# DM2097_BOOT_AUX_uSD.net
KiCad netlist of a schematic drawn in Altium Designer
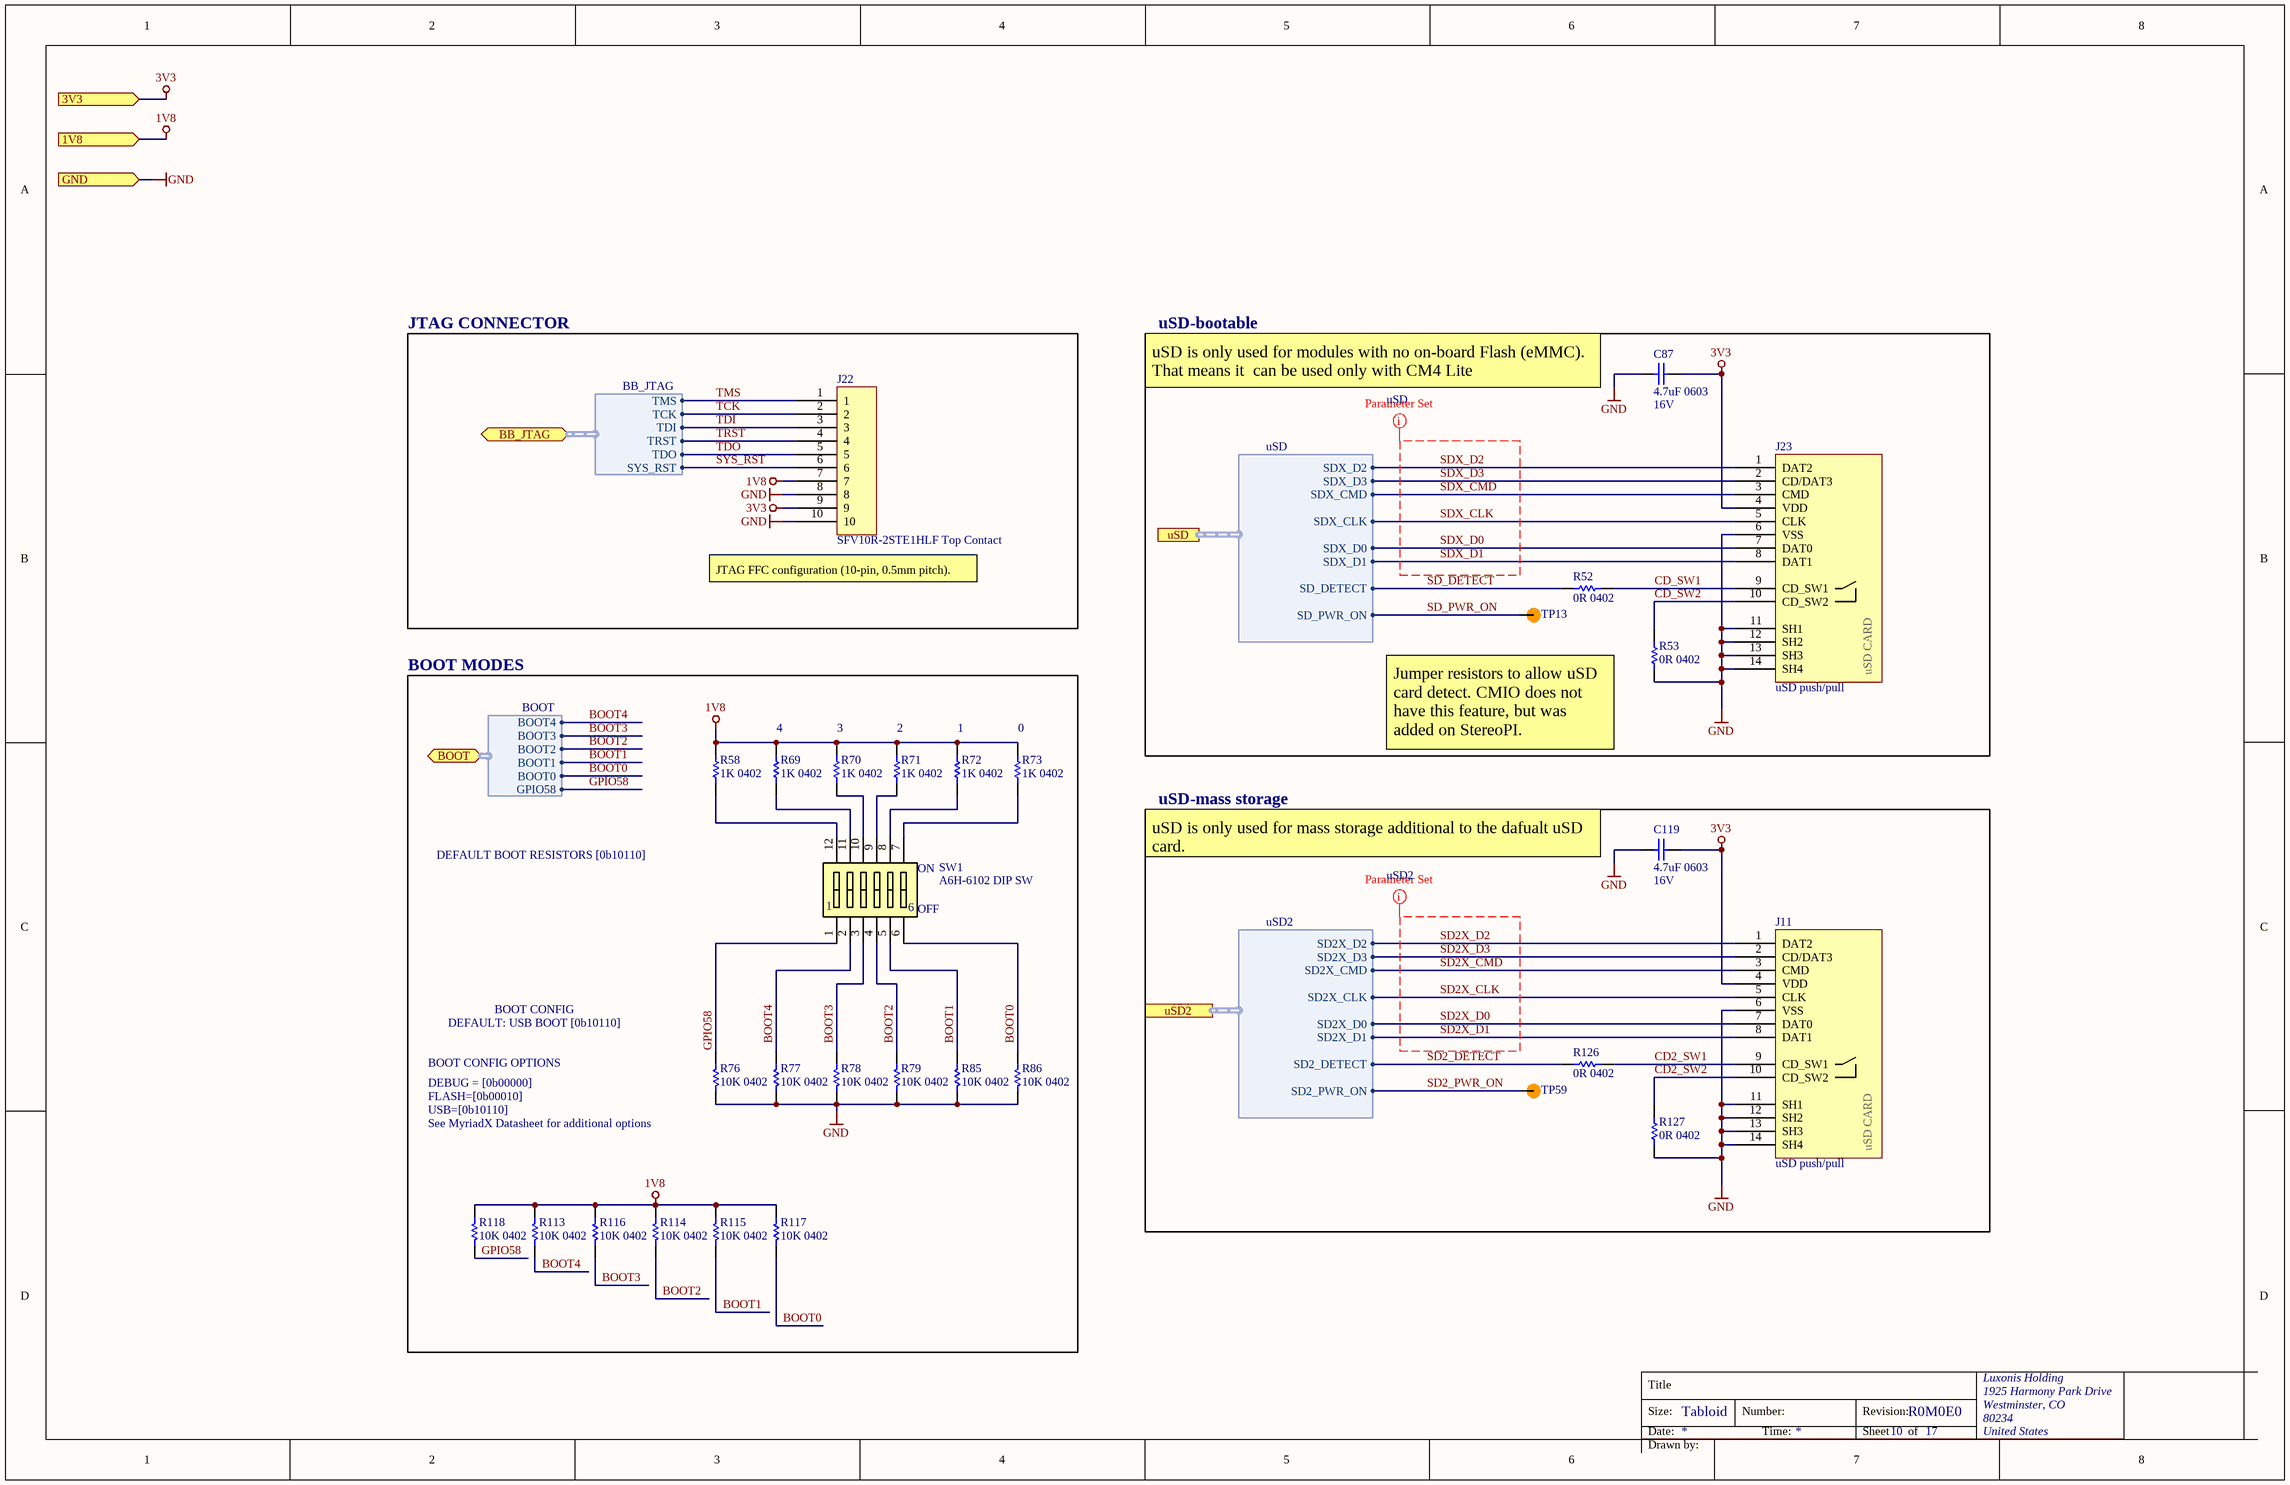
[diagram p0: DM2097_BOOT_AUX_uSD.SchDoc]

(export (version "E")
  (design (tool "Eeschema 10.0.6"))
  (components
    (comp (ref "C87")
      (value "4.7uF 0603")
      (footprint "CAP_Altium_Vault_Generic:CAPC0603(1608)100_N")
      (description "CAP CER 4.7UF 16V X5R 0603 10%")
      (fields (field (name "TOLERANCE") "10%") (field (name "VOLTAGE RATING") "16V"))
      (libsource (lib "LuxonisMaster") (part "GRM188R61C475KAAJD"))
    )
    (comp (ref "C119")
      (value "4.7uF 0603")
      (footprint "CAP_Altium_Vault_Generic:CAPC0603(1608)100_N")
      (description "CAP CER 4.7UF 16V X5R 0603 10%")
      (fields (field (name "TOLERANCE") "10%") (field (name "VOLTAGE RATING") "16V"))
      (libsource (lib "LuxonisMaster") (part "GRM188R61C475KAAJD"))
    )
    (comp (ref "J11")
      (value "uSD push/pull")
      (footprint "LuxonisMaster:104031-0811")
      (description "CONN MICRO SD CARD PUSH-PULL R/A")
      (libsource (lib "LuxonisMaster") (part "104031-0811"))
    )
    (comp (ref "J22")
      (value "SFV10R-2STE1HLF Top Contact")
      (footprint "LuxonisMaster:SFV10R-2STE1HLF")
      (description "CONN FFC TOP 10POS 0.50MM R/A")
      (libsource (lib "LuxonisMaster") (part "SFV10R-2STE1HLF"))
    )
    (comp (ref "J23")
      (value "uSD push/pull")
      (footprint "LuxonisMaster:104031-0811")
      (description "CONN MICRO SD CARD PUSH-PULL R/A")
      (libsource (lib "LuxonisMaster") (part "104031-0811"))
    )
    (comp (ref "R52")
      (value "0R 0402")
      (footprint "RES_Altium_Vault_Generic:RESC0402(1005)_N")
      (description "RES SMD 0 OHM JUMPER 1/16W 0402")
      (fields (field (name "TOLERANCE") "5%"))
      (libsource (lib "LuxonisMaster") (part "CRCW04020000Z0ED"))
    )
    (comp (ref "R53")
      (value "0R 0402")
      (footprint "RES_Altium_Vault_Generic:RESC0402(1005)_N")
      (description "RES SMD 0 OHM JUMPER 1/16W 0402")
      (fields (field (name "TOLERANCE") "5%"))
      (libsource (lib "LuxonisMaster") (part "CRCW04020000Z0ED"))
    )
    (comp (ref "R58")
      (value "1K 0402")
      (footprint "RES_Altium_Vault_Generic:RESC0402(1005)_N")
      (fields (field (name "TOLERANCE") "1%"))
      (libsource (lib "LuxonisMaster") (part "RC0402FR-071KL"))
    )
    (comp (ref "R69")
      (value "1K 0402")
      (footprint "RES_Altium_Vault_Generic:RESC0402(1005)_N")
      (fields (field (name "TOLERANCE") "1%"))
      (libsource (lib "LuxonisMaster") (part "RC0402FR-071KL"))
    )
    (comp (ref "R70")
      (value "1K 0402")
      (footprint "RES_Altium_Vault_Generic:RESC0402(1005)_N")
      (fields (field (name "TOLERANCE") "1%"))
      (libsource (lib "LuxonisMaster") (part "RC0402FR-071KL"))
    )
    (comp (ref "R71")
      (value "1K 0402")
      (footprint "RES_Altium_Vault_Generic:RESC0402(1005)_N")
      (fields (field (name "TOLERANCE") "1%"))
      (libsource (lib "LuxonisMaster") (part "RC0402FR-071KL"))
    )
    (comp (ref "R72")
      (value "1K 0402")
      (footprint "RES_Altium_Vault_Generic:RESC0402(1005)_N")
      (fields (field (name "TOLERANCE") "1%"))
      (libsource (lib "LuxonisMaster") (part "RC0402FR-071KL"))
    )
    (comp (ref "R73")
      (value "1K 0402")
      (footprint "RES_Altium_Vault_Generic:RESC0402(1005)_N")
      (fields (field (name "TOLERANCE") "1%"))
      (libsource (lib "LuxonisMaster") (part "RC0402FR-071KL"))
    )
    (comp (ref "R76")
      (value "10K 0402")
      (footprint "RES_Altium_Vault_Generic:RESC0402(1005)_N")
      (fields (field (name "TOLERANCE") "1%"))
      (libsource (lib "LuxonisMaster") (part "RC0402FR-1310KL"))
    )
    (comp (ref "R77")
      (value "10K 0402")
      (footprint "RES_Altium_Vault_Generic:RESC0402(1005)_N")
      (fields (field (name "TOLERANCE") "1%"))
      (libsource (lib "LuxonisMaster") (part "RC0402FR-1310KL"))
    )
    (comp (ref "R78")
      (value "10K 0402")
      (footprint "RES_Altium_Vault_Generic:RESC0402(1005)_N")
      (fields (field (name "TOLERANCE") "1%"))
      (libsource (lib "LuxonisMaster") (part "RC0402FR-1310KL"))
    )
    (comp (ref "R79")
      (value "10K 0402")
      (footprint "RES_Altium_Vault_Generic:RESC0402(1005)_N")
      (fields (field (name "TOLERANCE") "1%"))
      (libsource (lib "LuxonisMaster") (part "RC0402FR-1310KL"))
    )
    (comp (ref "R85")
      (value "10K 0402")
      (footprint "RES_Altium_Vault_Generic:RESC0402(1005)_N")
      (fields (field (name "TOLERANCE") "1%"))
      (libsource (lib "LuxonisMaster") (part "RC0402FR-1310KL"))
    )
    (comp (ref "R86")
      (value "10K 0402")
      (footprint "RES_Altium_Vault_Generic:RESC0402(1005)_N")
      (fields (field (name "TOLERANCE") "1%"))
      (libsource (lib "LuxonisMaster") (part "RC0402FR-1310KL"))
    )
    (comp (ref "R113")
      (value "10K 0402")
      (footprint "RES_Altium_Vault_Generic:RESC0402(1005)_N")
      (fields (field (name "TOLERANCE") "1%"))
      (libsource (lib "LuxonisMaster") (part "RC0402FR-1310KL"))
    )
    (comp (ref "R114")
      (value "10K 0402")
      (footprint "RES_Altium_Vault_Generic:RESC0402(1005)_N")
      (fields (field (name "TOLERANCE") "1%"))
      (libsource (lib "LuxonisMaster") (part "RC0402FR-1310KL"))
    )
    (comp (ref "R115")
      (value "10K 0402")
      (footprint "RES_Altium_Vault_Generic:RESC0402(1005)_N")
      (fields (field (name "TOLERANCE") "1%"))
      (libsource (lib "LuxonisMaster") (part "RC0402FR-1310KL"))
    )
    (comp (ref "R116")
      (value "10K 0402")
      (footprint "RES_Altium_Vault_Generic:RESC0402(1005)_N")
      (fields (field (name "TOLERANCE") "1%"))
      (libsource (lib "LuxonisMaster") (part "RC0402FR-1310KL"))
    )
    (comp (ref "R117")
      (value "10K 0402")
      (footprint "RES_Altium_Vault_Generic:RESC0402(1005)_N")
      (fields (field (name "TOLERANCE") "1%"))
      (libsource (lib "LuxonisMaster") (part "RC0402FR-1310KL"))
    )
    (comp (ref "R118")
      (value "10K 0402")
      (footprint "RES_Altium_Vault_Generic:RESC0402(1005)_N")
      (fields (field (name "TOLERANCE") "1%"))
      (libsource (lib "LuxonisMaster") (part "RC0402FR-1310KL"))
    )
    (comp (ref "R126")
      (value "0R 0402")
      (footprint "RES_Altium_Vault_Generic:RESC0402(1005)_N")
      (description "RES SMD 0 OHM JUMPER 1/16W 0402")
      (fields (field (name "TOLERANCE") "5%"))
      (libsource (lib "LuxonisMaster") (part "CRCW04020000Z0ED"))
    )
    (comp (ref "R127")
      (value "0R 0402")
      (footprint "RES_Altium_Vault_Generic:RESC0402(1005)_N")
      (description "RES SMD 0 OHM JUMPER 1/16W 0402")
      (fields (field (name "TOLERANCE") "5%"))
      (libsource (lib "LuxonisMaster") (part "CRCW04020000Z0ED"))
    )
    (comp (ref "SW1")
      (value "A6H-6102 DIP SW")
      (footprint "LuxonisMaster:A6H-610x")
      (description "SWITCH SLIDE DIP SPST 25MA 24V (SEALED)")
      (libsource (lib "LuxonisMaster") (part "A6H-6102"))
    )
    (comp (ref "TP13")
      (value "TP100_200_NS")
      (footprint "LuxonisMaster:TP100_200_NS")
      (libsource (lib "LuxonisMaster") (part "TEST_POINT"))
    )
    (comp (ref "TP59")
      (value "TP100_200_NS")
      (footprint "LuxonisMaster:TP100_200_NS")
      (libsource (lib "LuxonisMaster") (part "TEST_POINT"))
    )
  )
  (nets
    (net (code "5") (name "/BOOT0") (class "Default")
      (node (ref "R117") (pin "2") (pinfunction "2_2") (pintype "passive"))
      (node (ref "R86") (pin "1") (pinfunction "1_1") (pintype "passive"))
      (node (ref "SW1") (pin "6") (pinfunction "6_6") (pintype "passive"))
    )
    (net (code "6") (name "/BOOT1") (class "Default")
      (node (ref "R115") (pin "2") (pinfunction "2_2") (pintype "passive"))
      (node (ref "R85") (pin "1") (pinfunction "1_1") (pintype "passive"))
      (node (ref "SW1") (pin "5") (pinfunction "5_5") (pintype "passive"))
    )
    (net (code "7") (name "/BOOT2") (class "Default")
      (node (ref "R114") (pin "2") (pinfunction "2_2") (pintype "passive"))
      (node (ref "R79") (pin "1") (pinfunction "1_1") (pintype "passive"))
      (node (ref "SW1") (pin "4") (pinfunction "4_4") (pintype "passive"))
    )
    (net (code "8") (name "/BOOT3") (class "Default")
      (node (ref "R116") (pin "2") (pinfunction "2_2") (pintype "passive"))
      (node (ref "R78") (pin "1") (pinfunction "1_1") (pintype "passive"))
      (node (ref "SW1") (pin "3") (pinfunction "3_3") (pintype "passive"))
    )
    (net (code "9") (name "/BOOT4") (class "Default")
      (node (ref "R113") (pin "2") (pinfunction "2_2") (pintype "passive"))
      (node (ref "R77") (pin "1") (pinfunction "1_1") (pintype "passive"))
      (node (ref "SW1") (pin "2") (pinfunction "2_2") (pintype "passive"))
    )
    (net (code "10") (name "/CD2_SW1") (class "Default")
      (node (ref "J11") (pin "9") (pinfunction "CD_SW1_9") (pintype "passive"))
      (node (ref "R126") (pin "1") (pinfunction "1_1") (pintype "passive"))
    )
    (net (code "11") (name "/CD2_SW2") (class "Default")
      (node (ref "J11") (pin "10") (pinfunction "CD_SW2_10") (pintype "passive"))
      (node (ref "R127") (pin "2") (pinfunction "2_2") (pintype "passive"))
    )
    (net (code "12") (name "/CD_SW1") (class "Default")
      (node (ref "J23") (pin "9") (pinfunction "CD_SW1_9") (pintype "passive"))
      (node (ref "R52") (pin "1") (pinfunction "1_1") (pintype "passive"))
    )
    (net (code "13") (name "/CD_SW2") (class "Default")
      (node (ref "J23") (pin "10") (pinfunction "CD_SW2_10") (pintype "passive"))
      (node (ref "R53") (pin "2") (pinfunction "2_2") (pintype "passive"))
    )
    (net (code "14") (name "/GPIO58") (class "Default")
      (node (ref "R118") (pin "2") (pinfunction "2_2") (pintype "passive"))
      (node (ref "R76") (pin "1") (pinfunction "1_1") (pintype "passive"))
      (node (ref "SW1") (pin "1") (pinfunction "1_1") (pintype "passive"))
    )
    (net (code "15") (name "/SD2X_CLK") (class "Default")
      (node (ref "J11") (pin "5") (pinfunction "CLK_5") (pintype "passive"))
    )
    (net (code "16") (name "/SD2X_CMD") (class "Default")
      (node (ref "J11") (pin "3") (pinfunction "CMD_3") (pintype "passive"))
    )
    (net (code "17") (name "/SD2X_D0") (class "Default")
      (node (ref "J11") (pin "7") (pinfunction "DAT0_7") (pintype "passive"))
    )
    (net (code "18") (name "/SD2X_D1") (class "Default")
      (node (ref "J11") (pin "8") (pinfunction "DAT1_8") (pintype "passive"))
    )
    (net (code "19") (name "/SD2X_D2") (class "Default")
      (node (ref "J11") (pin "1") (pinfunction "DAT2_1") (pintype "passive"))
    )
    (net (code "20") (name "/SD2X_D3") (class "Default")
      (node (ref "J11") (pin "2") (pinfunction "CD/DAT3_2") (pintype "passive"))
    )
    (net (code "21") (name "/SD2_DETECT") (class "Default")
      (node (ref "R126") (pin "2") (pinfunction "2_2") (pintype "passive"))
    )
    (net (code "22") (name "/SD2_PWR_ON") (class "Default") (node (ref "TP59") (pin "1") (pintype "passive")))
    (net (code "23") (name "/SDX_CLK") (class "Default")
      (node (ref "J23") (pin "5") (pinfunction "CLK_5") (pintype "passive"))
    )
    (net (code "24") (name "/SDX_CMD") (class "Default")
      (node (ref "J23") (pin "3") (pinfunction "CMD_3") (pintype "passive"))
    )
    (net (code "25") (name "/SDX_D0") (class "Default")
      (node (ref "J23") (pin "7") (pinfunction "DAT0_7") (pintype "passive"))
    )
    (net (code "26") (name "/SDX_D1") (class "Default")
      (node (ref "J23") (pin "8") (pinfunction "DAT1_8") (pintype "passive"))
    )
    (net (code "27") (name "/SDX_D2") (class "Default")
      (node (ref "J23") (pin "1") (pinfunction "DAT2_1") (pintype "passive"))
    )
    (net (code "28") (name "/SDX_D3") (class "Default")
      (node (ref "J23") (pin "2") (pinfunction "CD/DAT3_2") (pintype "passive"))
    )
    (net (code "29") (name "/SD_DETECT") (class "Default")
      (node (ref "R52") (pin "2") (pinfunction "2_2") (pintype "passive"))
    )
    (net (code "30") (name "/SD_PWR_ON") (class "Default") (node (ref "TP13") (pin "1") (pintype "passive")))
    (net (code "31") (name "/SYS_RST") (class "Default")
      (node (ref "J22") (pin "6") (pinfunction "6_6") (pintype "passive"))
    )
    (net (code "32") (name "/TCK") (class "Default")
      (node (ref "J22") (pin "2") (pinfunction "2_2") (pintype "passive"))
    )
    (net (code "33") (name "/TDI") (class "Default")
      (node (ref "J22") (pin "3") (pinfunction "3_3") (pintype "passive"))
    )
    (net (code "34") (name "/TDO") (class "Default")
      (node (ref "J22") (pin "5") (pinfunction "5_5") (pintype "passive"))
    )
    (net (code "35") (name "/TMS") (class "Default")
      (node (ref "J22") (pin "1") (pinfunction "1_1") (pintype "passive"))
    )
    (net (code "36") (name "/TRST") (class "Default")
      (node (ref "J22") (pin "4") (pinfunction "4_4") (pintype "passive"))
    )
    (net (code "41") (name "1V8") (class "Default")
      (node (ref "J22") (pin "7") (pinfunction "7_7") (pintype "passive"))
      (node (ref "R113") (pin "1") (pinfunction "1_1") (pintype "passive"))
      (node (ref "R114") (pin "1") (pinfunction "1_1") (pintype "passive"))
      (node (ref "R115") (pin "1") (pinfunction "1_1") (pintype "passive"))
      (node (ref "R116") (pin "1") (pinfunction "1_1") (pintype "passive"))
      (node (ref "R117") (pin "1") (pinfunction "1_1") (pintype "passive"))
      (node (ref "R118") (pin "1") (pinfunction "1_1") (pintype "passive"))
      (node (ref "R58") (pin "2") (pinfunction "2_2") (pintype "passive"))
      (node (ref "R69") (pin "2") (pinfunction "2_2") (pintype "passive"))
      (node (ref "R70") (pin "2") (pinfunction "2_2") (pintype "passive"))
      (node (ref "R71") (pin "2") (pinfunction "2_2") (pintype "passive"))
      (node (ref "R72") (pin "2") (pinfunction "2_2") (pintype "passive"))
      (node (ref "R73") (pin "2") (pinfunction "2_2") (pintype "passive"))
    )
    (net (code "42") (name "3V3") (class "Default")
      (node (ref "C119") (pin "2") (pinfunction "2_2") (pintype "passive"))
      (node (ref "C87") (pin "2") (pinfunction "2_2") (pintype "passive"))
      (node (ref "J11") (pin "4") (pinfunction "VDD_4") (pintype "passive"))
      (node (ref "J22") (pin "9") (pinfunction "9_9") (pintype "passive"))
      (node (ref "J23") (pin "4") (pinfunction "VDD_4") (pintype "passive"))
    )
    (net (code "43") (name "GND") (class "Default")
      (node (ref "C119") (pin "1") (pinfunction "1_1") (pintype "passive"))
      (node (ref "C87") (pin "1") (pinfunction "1_1") (pintype "passive"))
      (node (ref "J11") (pin "11") (pinfunction "SH1_11") (pintype "passive"))
      (node (ref "J11") (pin "12") (pinfunction "SH2_12") (pintype "passive"))
      (node (ref "J11") (pin "13") (pinfunction "SH3_13") (pintype "passive"))
      (node (ref "J11") (pin "14") (pinfunction "SH4_14") (pintype "passive"))
      (node (ref "J11") (pin "6") (pinfunction "VSS_6") (pintype "passive"))
      (node (ref "J22") (pin "10") (pinfunction "10_10") (pintype "passive"))
      (node (ref "J22") (pin "8") (pinfunction "8_8") (pintype "passive"))
      (node (ref "J23") (pin "11") (pinfunction "SH1_11") (pintype "passive"))
      (node (ref "J23") (pin "12") (pinfunction "SH2_12") (pintype "passive"))
      (node (ref "J23") (pin "13") (pinfunction "SH3_13") (pintype "passive"))
      (node (ref "J23") (pin "14") (pinfunction "SH4_14") (pintype "passive"))
      (node (ref "J23") (pin "6") (pinfunction "VSS_6") (pintype "passive"))
      (node (ref "R127") (pin "1") (pinfunction "1_1") (pintype "passive"))
      (node (ref "R53") (pin "1") (pinfunction "1_1") (pintype "passive"))
      (node (ref "R76") (pin "2") (pinfunction "2_2") (pintype "passive"))
      (node (ref "R77") (pin "2") (pinfunction "2_2") (pintype "passive"))
      (node (ref "R78") (pin "2") (pinfunction "2_2") (pintype "passive"))
      (node (ref "R79") (pin "2") (pinfunction "2_2") (pintype "passive"))
      (node (ref "R85") (pin "2") (pinfunction "2_2") (pintype "passive"))
      (node (ref "R86") (pin "2") (pinfunction "2_2") (pintype "passive"))
    )
    (net (code "44") (name "Net-(R58-Pad1)") (class "Default")
      (node (ref "R58") (pin "1") (pinfunction "1_1") (pintype "passive"))
      (node (ref "SW1") (pin "12") (pinfunction "12_12") (pintype "passive"))
    )
    (net (code "45") (name "Net-(R69-Pad1)") (class "Default")
      (node (ref "R69") (pin "1") (pinfunction "1_1") (pintype "passive"))
      (node (ref "SW1") (pin "11") (pinfunction "11_11") (pintype "passive"))
    )
    (net (code "46") (name "Net-(R70-Pad1)") (class "Default")
      (node (ref "R70") (pin "1") (pinfunction "1_1") (pintype "passive"))
      (node (ref "SW1") (pin "10") (pinfunction "10_10") (pintype "passive"))
    )
    (net (code "47") (name "Net-(R71-Pad1)") (class "Default")
      (node (ref "R71") (pin "1") (pinfunction "1_1") (pintype "passive"))
      (node (ref "SW1") (pin "9") (pinfunction "9_9") (pintype "passive"))
    )
    (net (code "48") (name "Net-(R72-Pad1)") (class "Default")
      (node (ref "R72") (pin "1") (pinfunction "1_1") (pintype "passive"))
      (node (ref "SW1") (pin "8") (pinfunction "8_8") (pintype "passive"))
    )
    (net (code "49") (name "Net-(R73-Pad1)") (class "Default")
      (node (ref "R73") (pin "1") (pinfunction "1_1") (pintype "passive"))
      (node (ref "SW1") (pin "7") (pinfunction "7_7") (pintype "passive"))
    )
  )
)
